# DRV8301_1.net
KiCad netlist of a schematic drawn in Altium Designer
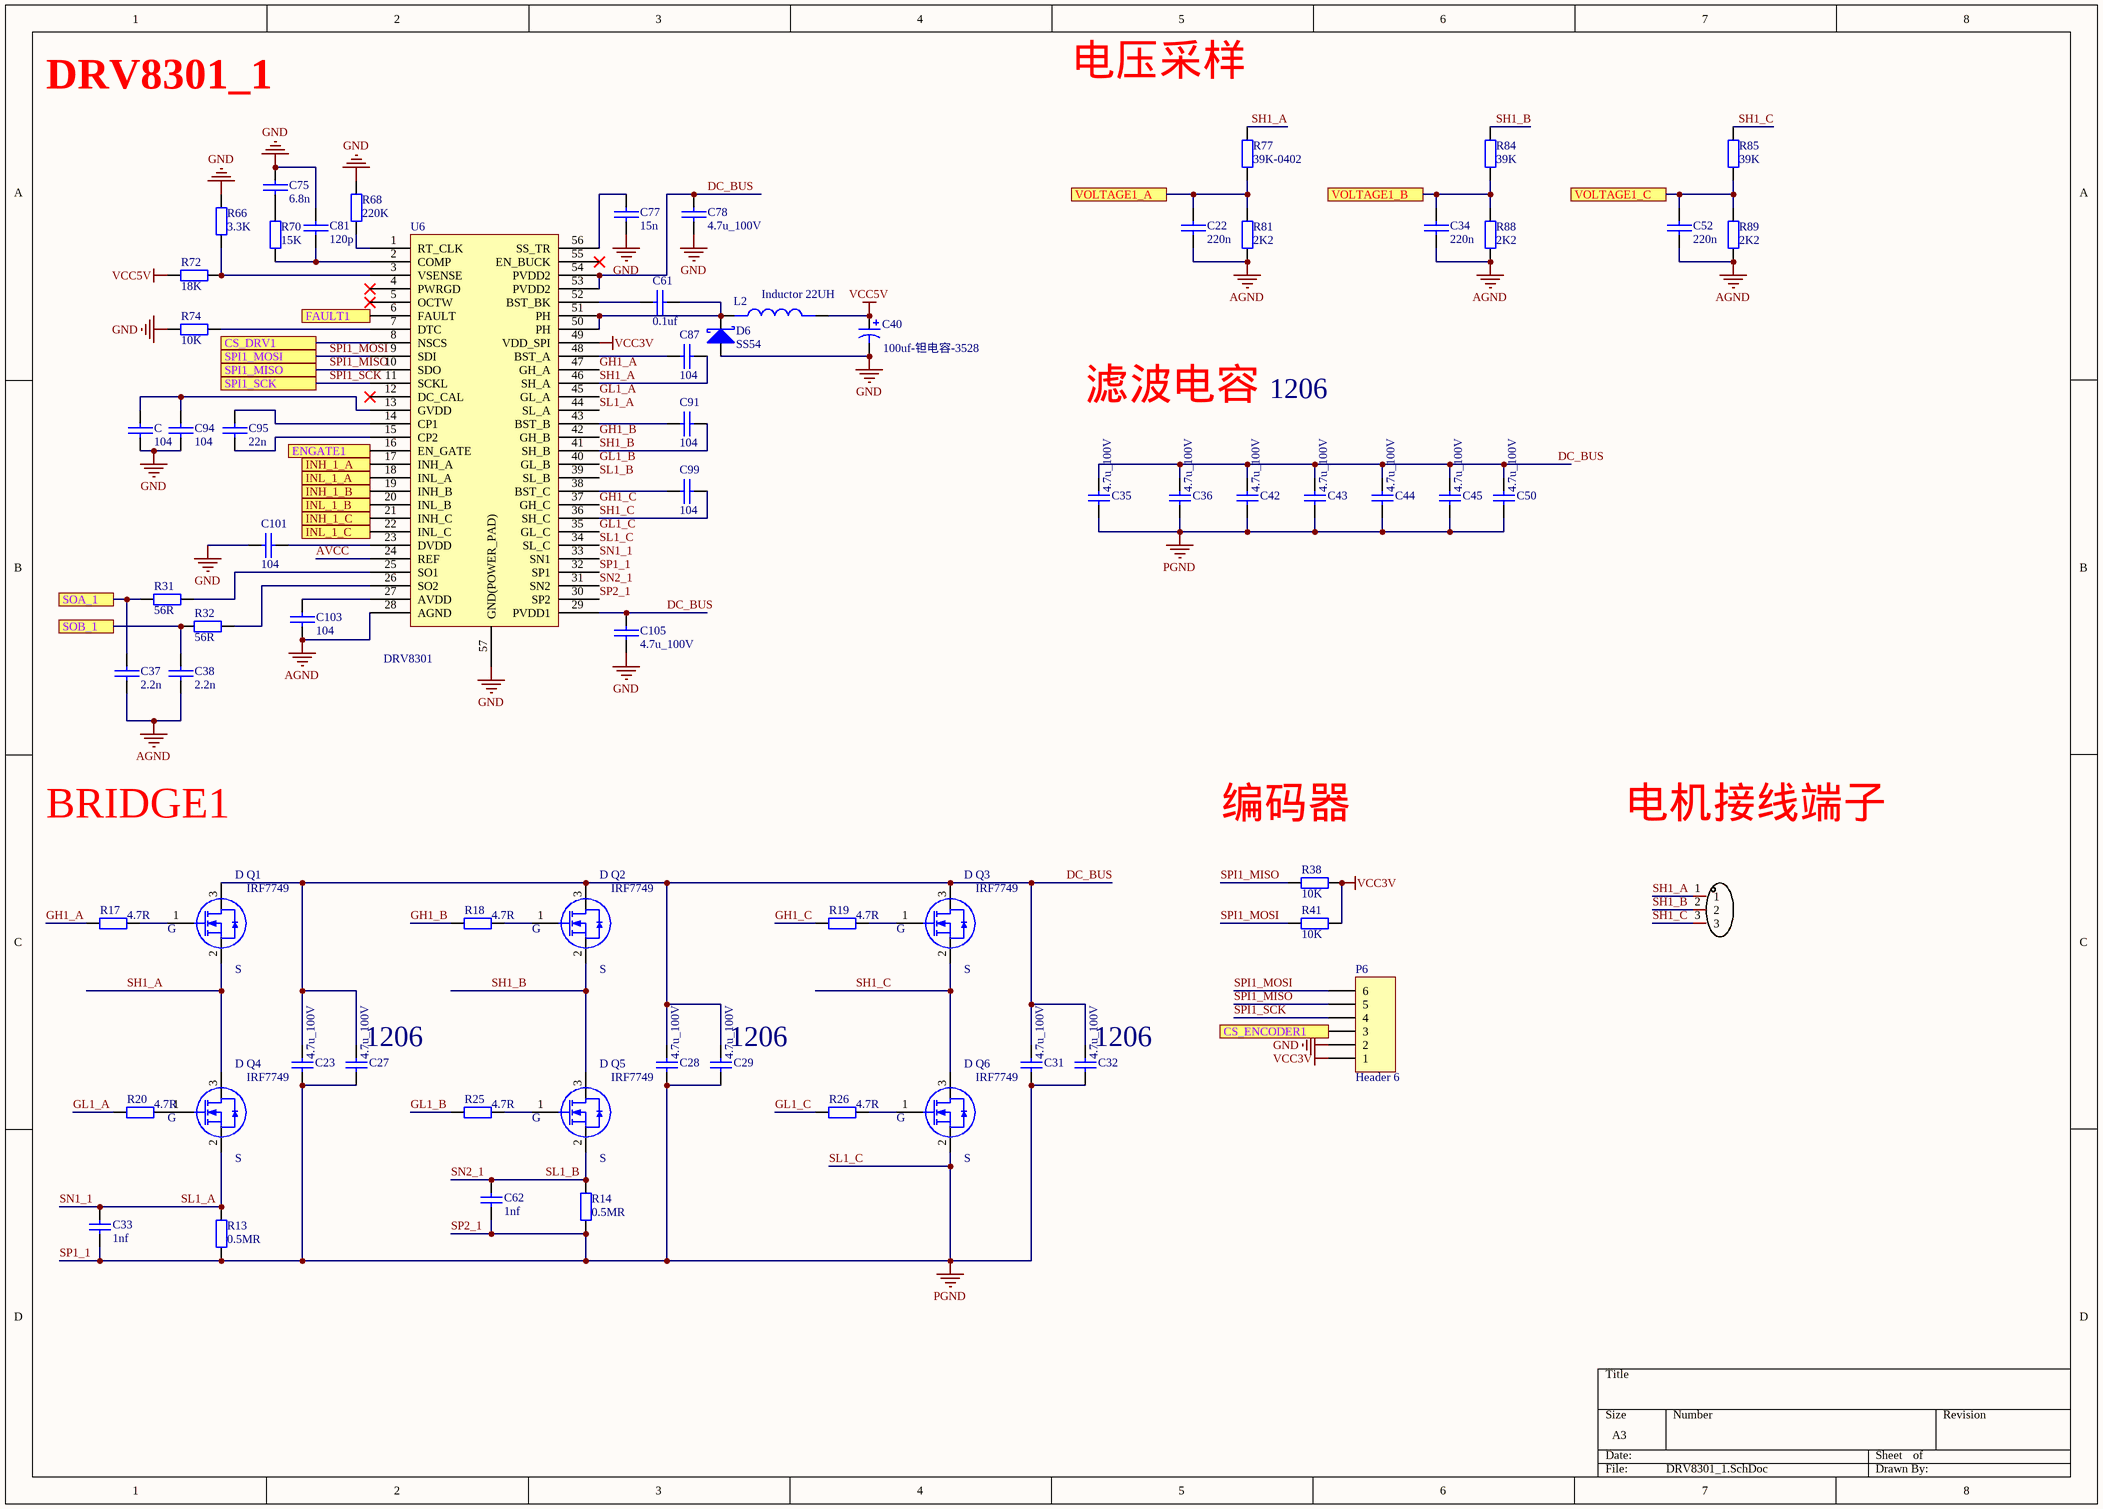
[diagram p0: DRV8301_1.SchDoc]

(export (version "E")
  (design (tool "Eeschema 10.0.6"))
  (components
    (comp (ref "C")
      (value "104")
      (footprint "0402C")
      (fields (field (name "Comment") "CAP"))
      (libsource (lib "MY SCH LIB__JCH") (part "CAP"))
    )
    (comp (ref "C22")
      (value "220n")
      (footprint "0402C")
      (fields (field (name "Comment") "CAP"))
      (libsource (lib "MY SCH LIB__JCH") (part "CAP"))
    )
    (comp (ref "C23")
      (value "4.7u_100V")
      (footprint "1206_C")
      (description "无极性电容")
      (fields (field (name "Comment") "Cap") (field (name "PUBLISHER") "Altium Limited"))
      (libsource (lib "Panel_Point") (part "Cap_6"))
    )
    (comp (ref "C27")
      (value "4.7u_100V")
      (footprint "1206_C")
      (description "无极性电容")
      (fields (field (name "Comment") "Cap") (field (name "PUBLISHER") "Altium Limited"))
      (libsource (lib "Panel_Point") (part "Cap_6"))
    )
    (comp (ref "C28")
      (value "4.7u_100V")
      (footprint "1206_C")
      (description "无极性电容")
      (fields (field (name "Comment") "Cap") (field (name "PUBLISHER") "Altium Limited"))
      (libsource (lib "Panel_Point") (part "Cap_6"))
    )
    (comp (ref "C29")
      (value "4.7u_100V")
      (footprint "1206_C")
      (description "无极性电容")
      (fields (field (name "Comment") "Cap") (field (name "PUBLISHER") "Altium Limited"))
      (libsource (lib "Panel_Point") (part "Cap_6"))
    )
    (comp (ref "C31")
      (value "4.7u_100V")
      (footprint "1206_C")
      (description "无极性电容")
      (fields (field (name "Comment") "Cap") (field (name "PUBLISHER") "Altium Limited"))
      (libsource (lib "Panel_Point") (part "Cap_6"))
    )
    (comp (ref "C32")
      (value "4.7u_100V")
      (footprint "1206_C")
      (description "无极性电容")
      (fields (field (name "Comment") "Cap") (field (name "PUBLISHER") "Altium Limited"))
      (libsource (lib "Panel_Point") (part "Cap_6"))
    )
    (comp (ref "C33")
      (value "1nf")
      (footprint "0402C")
      (description "无极性电容")
      (fields (field (name "Comment") "Cap") (field (name "PUBLISHER") "Altium Limited"))
      (libsource (lib "Panel_Point") (part "Cap_6"))
    )
    (comp (ref "C34")
      (value "220n")
      (footprint "0402C")
      (fields (field (name "Comment") "CAP"))
      (libsource (lib "MY SCH LIB__JCH") (part "CAP"))
    )
    (comp (ref "C35")
      (value "4.7u_100V")
      (footprint "1206_C")
      (description "无极性电容")
      (fields (field (name "Comment") "Cap") (field (name "PUBLISHER") "Altium Limited"))
      (libsource (lib "Panel_Point") (part "Cap_6"))
    )
    (comp (ref "C36")
      (value "4.7u_100V")
      (footprint "1206_C")
      (description "无极性电容")
      (fields (field (name "Comment") "Cap") (field (name "PUBLISHER") "Altium Limited"))
      (libsource (lib "Panel_Point") (part "Cap_6"))
    )
    (comp (ref "C37")
      (value "2.2n")
      (footprint "0402C")
      (fields (field (name "Comment") "CAP"))
      (libsource (lib "MY SCH LIB__JCH") (part "CAP"))
    )
    (comp (ref "C38")
      (value "2.2n")
      (footprint "0402C")
      (fields (field (name "Comment") "CAP"))
      (libsource (lib "MY SCH LIB__JCH") (part "CAP"))
    )
    (comp (ref "C40")
      (value "100uf-钽电容-3528")
      (footprint "CAP-SMD_L3.5-W2.8-R-RD")
      (fields (field (name "Comment") "CAP_HER"))
      (libsource (lib "FOC") (part "CAP_HER"))
    )
    (comp (ref "C42")
      (value "4.7u_100V")
      (footprint "1206_C")
      (description "无极性电容")
      (fields (field (name "Comment") "Cap") (field (name "PUBLISHER") "Altium Limited"))
      (libsource (lib "Panel_Point") (part "Cap_6"))
    )
    (comp (ref "C43")
      (value "4.7u_100V")
      (footprint "1206_C")
      (description "无极性电容")
      (fields (field (name "Comment") "Cap") (field (name "PUBLISHER") "Altium Limited"))
      (libsource (lib "Panel_Point") (part "Cap_6"))
    )
    (comp (ref "C44")
      (value "4.7u_100V")
      (footprint "1206_C")
      (description "无极性电容")
      (fields (field (name "Comment") "Cap") (field (name "PUBLISHER") "Altium Limited"))
      (libsource (lib "Panel_Point") (part "Cap_6"))
    )
    (comp (ref "C45")
      (value "4.7u_100V")
      (footprint "1206_C")
      (description "无极性电容")
      (fields (field (name "Comment") "Cap") (field (name "PUBLISHER") "Altium Limited"))
      (libsource (lib "Panel_Point") (part "Cap_6"))
    )
    (comp (ref "C50")
      (value "4.7u_100V")
      (footprint "1206_C")
      (description "无极性电容")
      (fields (field (name "Comment") "Cap") (field (name "PUBLISHER") "Altium Limited"))
      (libsource (lib "Panel_Point") (part "Cap_6"))
    )
    (comp (ref "C52")
      (value "220n")
      (footprint "0402C")
      (fields (field (name "Comment") "CAP"))
      (libsource (lib "MY SCH LIB__JCH") (part "CAP"))
    )
    (comp (ref "C61")
      (value "0.1uf")
      (footprint "0402C")
      (fields (field (name "Comment") "CAP"))
      (libsource (lib "MY SCH LIB__JCH") (part "CAP"))
    )
    (comp (ref "C62")
      (value "1nf")
      (footprint "0402C")
      (description "无极性电容")
      (fields (field (name "Comment") "Cap") (field (name "PUBLISHER") "Altium Limited"))
      (libsource (lib "Panel_Point") (part "Cap_6"))
    )
    (comp (ref "C75")
      (value "6.8n")
      (footprint "0402C")
      (fields (field (name "Comment") "CAP"))
      (libsource (lib "MY SCH LIB__JCH") (part "CAP"))
    )
    (comp (ref "C77")
      (value "15n")
      (footprint "0402C")
      (fields (field (name "Comment") "CAP"))
      (libsource (lib "MY SCH LIB__JCH") (part "CAP"))
    )
    (comp (ref "C78")
      (value "4.7u_100V")
      (footprint "0603_C")
      (fields (field (name "Comment") "CAP"))
      (libsource (lib "MY SCH LIB__JCH") (part "CAP"))
    )
    (comp (ref "C81")
      (value "120p")
      (footprint "0402C")
      (fields (field (name "Comment") "CAP"))
      (libsource (lib "MY SCH LIB__JCH") (part "CAP"))
    )
    (comp (ref "C87")
      (value "104")
      (footprint "0402C")
      (fields (field (name "Comment") "CAP"))
      (libsource (lib "MY SCH LIB__JCH") (part "CAP"))
    )
    (comp (ref "C91")
      (value "104")
      (footprint "0402C")
      (fields (field (name "Comment") "CAP"))
      (libsource (lib "MY SCH LIB__JCH") (part "CAP"))
    )
    (comp (ref "C94")
      (value "104")
      (footprint "0402C")
      (fields (field (name "Comment") "CAP"))
      (libsource (lib "MY SCH LIB__JCH") (part "CAP"))
    )
    (comp (ref "C95")
      (value "22n")
      (footprint "0402C")
      (fields (field (name "Comment") "CAP"))
      (libsource (lib "MY SCH LIB__JCH") (part "CAP"))
    )
    (comp (ref "C99")
      (value "104")
      (footprint "0402C")
      (fields (field (name "Comment") "CAP"))
      (libsource (lib "MY SCH LIB__JCH") (part "CAP"))
    )
    (comp (ref "C101")
      (value "104")
      (footprint "0402C")
      (fields (field (name "Comment") "CAP"))
      (libsource (lib "MY SCH LIB__JCH") (part "CAP"))
    )
    (comp (ref "C103")
      (value "104")
      (footprint "0402C")
      (fields (field (name "Comment") "CAP"))
      (libsource (lib "MY SCH LIB__JCH") (part "CAP"))
    )
    (comp (ref "C105")
      (value "4.7u_100V")
      (footprint "0603_C")
      (fields (field (name "Comment") "CAP"))
      (libsource (lib "MY SCH LIB__JCH") (part "CAP"))
    )
    (comp (ref "D6")
      (value "SS54")
      (footprint "DIODE_3*5.3")
      (description "Schottky Diode")
      (fields (field (name "PUBLISHER") "Altium Limited"))
      (libsource (lib "FOC") (part "D Schottky"))
    )
    (comp (ref "L2")
      (value "Inductor 22UH")
      (footprint "IND-SMD_L5.0-W5.0")
      (libsource (lib "Panel_Point") (part "IND"))
    )
    (comp (ref "P6")
      (value "Header 6")
      (footprint "A1002WR-S-6P")
      (description "Header, 6-Pin")
      (fields (field (name "PUBLISHER") "Altium Limited"))
      (libsource (lib "FOC") (part "Header 6"))
    )
    (comp (ref "Q1")
      (value "IRF7749")
      (footprint "IRF7480")
      (description "MOS(场效应管)")
      (libsource (lib "FOC") (part "IRF7749"))
    )
    (comp (ref "Q2")
      (value "IRF7749")
      (footprint "IRF7480")
      (description "MOS(场效应管)")
      (libsource (lib "FOC") (part "IRF7749"))
    )
    (comp (ref "Q3")
      (value "IRF7749")
      (footprint "IRF7480")
      (description "MOS(场效应管)")
      (libsource (lib "FOC") (part "IRF7749"))
    )
    (comp (ref "Q4")
      (value "IRF7749")
      (footprint "IRF7480")
      (description "MOS(场效应管)")
      (libsource (lib "FOC") (part "IRF7749"))
    )
    (comp (ref "Q5")
      (value "IRF7749")
      (footprint "IRF7480")
      (description "MOS(场效应管)")
      (libsource (lib "FOC") (part "IRF7749"))
    )
    (comp (ref "Q6")
      (value "IRF7749")
      (footprint "IRF7480")
      (description "MOS(场效应管)")
      (libsource (lib "FOC") (part "IRF7749"))
    )
    (comp (ref "R13")
      (value "0.5MR")
      (footprint "0.5mr_6W")
      (description "贴片电阻")
      (fields (field (name "Comment") "Res1") (field (name "PUBLISHER") "Altium Limited"))
      (libsource (lib "SMC_Devices") (part "Res1"))
    )
    (comp (ref "R14")
      (value "0.5MR")
      (footprint "0.5mr_6W")
      (description "贴片电阻")
      (fields (field (name "Comment") "Res1") (field (name "PUBLISHER") "Altium Limited"))
      (libsource (lib "SMC_Devices") (part "Res1"))
    )
    (comp (ref "R17")
      (value "4.7R")
      (footprint "0402R")
      (description "贴片电阻")
      (fields (field (name "Comment") "Res1") (field (name "PUBLISHER") "Altium Limited"))
      (libsource (lib "") (part "Res1_1"))
    )
    (comp (ref "R18")
      (value "4.7R")
      (footprint "0402R")
      (description "贴片电阻")
      (fields (field (name "Comment") "Res1") (field (name "PUBLISHER") "Altium Limited"))
      (libsource (lib "") (part "Res1_1"))
    )
    (comp (ref "R19")
      (value "4.7R")
      (footprint "0402R")
      (description "贴片电阻")
      (fields (field (name "Comment") "Res1") (field (name "PUBLISHER") "Altium Limited"))
      (libsource (lib "") (part "Res1_1"))
    )
    (comp (ref "R20")
      (value "4.7R")
      (footprint "0402R")
      (description "贴片电阻")
      (fields (field (name "Comment") "Res1") (field (name "PUBLISHER") "Altium Limited"))
      (libsource (lib "") (part "Res1_1"))
    )
    (comp (ref "R25")
      (value "4.7R")
      (footprint "0402R")
      (description "贴片电阻")
      (fields (field (name "Comment") "Res1") (field (name "PUBLISHER") "Altium Limited"))
      (libsource (lib "") (part "Res1_1"))
    )
    (comp (ref "R26")
      (value "4.7R")
      (footprint "0402R")
      (description "贴片电阻")
      (fields (field (name "Comment") "Res1") (field (name "PUBLISHER") "Altium Limited"))
      (libsource (lib "") (part "Res1_1"))
    )
    (comp (ref "R31")
      (value "56R")
      (footprint "0402R")
      (description "Resistor")
      (fields (field (name "PUBLISHER") "Altium Limited"))
      (libsource (lib "") (part "Res2_2"))
    )
    (comp (ref "R32")
      (value "56R")
      (footprint "0402R")
      (description "Resistor")
      (fields (field (name "PUBLISHER") "Altium Limited"))
      (libsource (lib "") (part "Res2_2"))
    )
    (comp (ref "R38")
      (value "10K")
      (footprint "0402R")
      (description "Resistor")
      (fields (field (name "PUBLISHER") "Altium Limited"))
      (libsource (lib "") (part "Res2_2"))
    )
    (comp (ref "R41")
      (value "10K")
      (footprint "0402R")
      (description "Resistor")
      (fields (field (name "PUBLISHER") "Altium Limited"))
      (libsource (lib "") (part "Res2_2"))
    )
    (comp (ref "R66")
      (value "3.3K")
      (footprint "0402R")
      (description "Resistor")
      (fields (field (name "PUBLISHER") "Altium Limited"))
      (libsource (lib "") (part "Res2_1"))
    )
    (comp (ref "R68")
      (value "220K")
      (footprint "0402R")
      (description "Resistor")
      (fields (field (name "PUBLISHER") "Altium Limited"))
      (libsource (lib "") (part "Res2_1"))
    )
    (comp (ref "R70")
      (value "15K")
      (footprint "0402R")
      (description "Resistor")
      (fields (field (name "PUBLISHER") "Altium Limited"))
      (libsource (lib "") (part "Res2_1"))
    )
    (comp (ref "R72")
      (value "18K")
      (footprint "0402R")
      (description "Resistor")
      (fields (field (name "PUBLISHER") "Altium Limited"))
      (libsource (lib "") (part "Res2_2"))
    )
    (comp (ref "R74")
      (value "10K")
      (footprint "0402R")
      (description "Resistor")
      (fields (field (name "PUBLISHER") "Altium Limited"))
      (libsource (lib "") (part "Res2_2"))
    )
    (comp (ref "R77")
      (value "39K-0402")
      (footprint "0402R")
      (description "Resistor")
      (fields (field (name "PUBLISHER") "Altium Limited"))
      (libsource (lib "") (part "Res2_1"))
    )
    (comp (ref "R81")
      (value "2K2")
      (footprint "0402R")
      (description "Resistor")
      (fields (field (name "PUBLISHER") "Altium Limited"))
      (libsource (lib "Miscellaneous Devices") (part "Res2"))
    )
    (comp (ref "R84")
      (value "39K")
      (footprint "0402R")
      (description "Resistor")
      (fields (field (name "PUBLISHER") "Altium Limited"))
      (libsource (lib "") (part "Res2_1"))
    )
    (comp (ref "R85")
      (value "39K")
      (footprint "0402R")
      (description "Resistor")
      (fields (field (name "PUBLISHER") "Altium Limited"))
      (libsource (lib "") (part "Res2_1"))
    )
    (comp (ref "R88")
      (value "2K2")
      (footprint "0402R")
      (description "Resistor")
      (fields (field (name "PUBLISHER") "Altium Limited"))
      (libsource (lib "Miscellaneous Devices") (part "Res2"))
    )
    (comp (ref "R89")
      (value "2K2")
      (footprint "0402R")
      (description "Resistor")
      (fields (field (name "PUBLISHER") "Altium Limited"))
      (libsource (lib "Miscellaneous Devices") (part "Res2"))
    )
    (comp (ref "U6")
      (value "DRV8301")
      (footprint "HTSSOP-56_L14.0-W6.0-P0.50-LS8.0-BL")
      (description "三相整流桥芯片")
      (libsource (lib "FOC") (part "DRV8301"))
    )
    (comp (ref "U7")
      (value "MR30-M")
      (footprint "MR30-M-SMD")
      (fields (field (name "MANUFACTURER") "AMASS(艾迈斯)"))
      (libsource (lib "FOC") (part "MR30-M"))
    )
  )
  (nets
    (net (code "1") (name "/AVCC") (class "Default")
      (node (ref "U6") (pin "24") (pinfunction "REF_24") (pintype "passive"))
    )
    (net (code "2") (name "/CS_DRV1") (class "Default")
      (node (ref "U6") (pin "8") (pinfunction "NSCS_8") (pintype "passive"))
    )
    (net (code "3") (name "/CS_ENCODER1") (class "Default")
      (node (ref "P6") (pin "3") (pinfunction "3_3") (pintype "passive"))
    )
    (net (code "4") (name "/DC_BUS") (class "Default")
      (node (ref "C105") (pin "2") (pinfunction "2_2") (pintype "passive"))
      (node (ref "C23") (pin "2") (pinfunction "2_2") (pintype "passive"))
      (node (ref "C27") (pin "2") (pinfunction "2_2") (pintype "passive"))
      (node (ref "C28") (pin "2") (pinfunction "2_2") (pintype "passive"))
      (node (ref "C29") (pin "2") (pinfunction "2_2") (pintype "passive"))
      (node (ref "C31") (pin "2") (pinfunction "2_2") (pintype "passive"))
      (node (ref "C32") (pin "2") (pinfunction "2_2") (pintype "passive"))
      (node (ref "C35") (pin "2") (pinfunction "2_2") (pintype "passive"))
      (node (ref "C36") (pin "2") (pinfunction "2_2") (pintype "passive"))
      (node (ref "C42") (pin "2") (pinfunction "2_2") (pintype "passive"))
      (node (ref "C43") (pin "2") (pinfunction "2_2") (pintype "passive"))
      (node (ref "C44") (pin "2") (pinfunction "2_2") (pintype "passive"))
      (node (ref "C45") (pin "2") (pinfunction "2_2") (pintype "passive"))
      (node (ref "C50") (pin "2") (pinfunction "2_2") (pintype "passive"))
      (node (ref "C78") (pin "2") (pinfunction "2_2") (pintype "passive"))
      (node (ref "Q1") (pin "3") (pinfunction "D_3") (pintype "passive"))
      (node (ref "Q2") (pin "3") (pinfunction "D_3") (pintype "passive"))
      (node (ref "Q3") (pin "3") (pinfunction "D_3") (pintype "passive"))
      (node (ref "U6") (pin "29") (pinfunction "PVDD1_29") (pintype "passive"))
      (node (ref "U6") (pin "53") (pinfunction "PVDD2_53") (pintype "passive"))
      (node (ref "U6") (pin "54") (pinfunction "PVDD2_54") (pintype "passive"))
    )
    (net (code "5") (name "/ENGATE1") (class "Default")
      (node (ref "U6") (pin "16") (pinfunction "EN_GATE_16") (pintype "passive"))
    )
    (net (code "6") (name "/FAULT1") (class "Default")
      (node (ref "U6") (pin "6") (pinfunction "FAULT_6") (pintype "passive"))
    )
    (net (code "7") (name "/GH1_A") (class "Default")
      (node (ref "R17") (pin "1") (pinfunction "1_1") (pintype "passive"))
      (node (ref "U6") (pin "47") (pinfunction "GH_A_47") (pintype "passive"))
    )
    (net (code "8") (name "/GH1_B") (class "Default")
      (node (ref "R18") (pin "1") (pinfunction "1_1") (pintype "passive"))
      (node (ref "U6") (pin "42") (pinfunction "GH_B_42") (pintype "passive"))
    )
    (net (code "9") (name "/GH1_C") (class "Default")
      (node (ref "R19") (pin "1") (pinfunction "1_1") (pintype "passive"))
      (node (ref "U6") (pin "37") (pinfunction "GH_C_37") (pintype "passive"))
    )
    (net (code "10") (name "/GL1_A") (class "Default")
      (node (ref "R20") (pin "1") (pinfunction "1_1") (pintype "passive"))
      (node (ref "U6") (pin "45") (pinfunction "GL_A_45") (pintype "passive"))
    )
    (net (code "11") (name "/GL1_B") (class "Default")
      (node (ref "R25") (pin "1") (pinfunction "1_1") (pintype "passive"))
      (node (ref "U6") (pin "40") (pinfunction "GL_B_40") (pintype "passive"))
    )
    (net (code "12") (name "/GL1_C") (class "Default")
      (node (ref "R26") (pin "1") (pinfunction "1_1") (pintype "passive"))
      (node (ref "U6") (pin "35") (pinfunction "GL_C_35") (pintype "passive"))
    )
    (net (code "13") (name "/INH_1_A") (class "Default")
      (node (ref "U6") (pin "17") (pinfunction "INH_A_17") (pintype "passive"))
    )
    (net (code "14") (name "/INH_1_B") (class "Default")
      (node (ref "U6") (pin "19") (pinfunction "INH_B_19") (pintype "passive"))
    )
    (net (code "15") (name "/INH_1_C") (class "Default")
      (node (ref "U6") (pin "21") (pinfunction "INH_C_21") (pintype "passive"))
    )
    (net (code "16") (name "/INL_1_A") (class "Default")
      (node (ref "U6") (pin "18") (pinfunction "INL_A_18") (pintype "passive"))
    )
    (net (code "17") (name "/INL_1_B") (class "Default")
      (node (ref "U6") (pin "20") (pinfunction "INL_B_20") (pintype "passive"))
    )
    (net (code "18") (name "/INL_1_C") (class "Default")
      (node (ref "U6") (pin "22") (pinfunction "INL_C_22") (pintype "passive"))
    )
    (net (code "19") (name "/SH1_A") (class "Default")
      (node (ref "C87") (pin "1") (pinfunction "1_1") (pintype "passive"))
      (node (ref "Q1") (pin "2") (pinfunction "S_2") (pintype "passive"))
      (node (ref "Q4") (pin "3") (pinfunction "D_3") (pintype "passive"))
      (node (ref "R77") (pin "2") (pinfunction "2_2") (pintype "passive"))
      (node (ref "U6") (pin "46") (pinfunction "SH_A_46") (pintype "passive"))
      (node (ref "U7") (pin "1") (pinfunction "1_1") (pintype "passive"))
    )
    (net (code "20") (name "/SH1_B") (class "Default")
      (node (ref "C91") (pin "1") (pinfunction "1_1") (pintype "passive"))
      (node (ref "Q2") (pin "2") (pinfunction "S_2") (pintype "passive"))
      (node (ref "Q5") (pin "3") (pinfunction "D_3") (pintype "passive"))
      (node (ref "R84") (pin "2") (pinfunction "2_2") (pintype "passive"))
      (node (ref "U6") (pin "41") (pinfunction "SH_B_41") (pintype "passive"))
      (node (ref "U7") (pin "2") (pinfunction "2_2") (pintype "passive"))
    )
    (net (code "21") (name "/SH1_C") (class "Default")
      (node (ref "C99") (pin "1") (pinfunction "1_1") (pintype "passive"))
      (node (ref "Q3") (pin "2") (pinfunction "S_2") (pintype "passive"))
      (node (ref "Q6") (pin "3") (pinfunction "D_3") (pintype "passive"))
      (node (ref "R85") (pin "2") (pinfunction "2_2") (pintype "passive"))
      (node (ref "U6") (pin "36") (pinfunction "SH_C_36") (pintype "passive"))
      (node (ref "U7") (pin "3") (pinfunction "3_3") (pintype "passive"))
    )
    (net (code "22") (name "/SL1_A") (class "Default")
      (node (ref "C33") (pin "2") (pinfunction "2_2") (pintype "passive"))
      (node (ref "Q4") (pin "2") (pinfunction "S_2") (pintype "passive"))
      (node (ref "R13") (pin "2") (pinfunction "2_2") (pintype "passive"))
      (node (ref "U6") (pin "33") (pinfunction "SN1_33") (pintype "passive"))
      (node (ref "U6") (pin "44") (pinfunction "SL_A_44") (pintype "passive"))
    )
    (net (code "23") (name "/SL1_B") (class "Default")
      (node (ref "C62") (pin "2") (pinfunction "2_2") (pintype "passive"))
      (node (ref "Q5") (pin "2") (pinfunction "S_2") (pintype "passive"))
      (node (ref "R14") (pin "2") (pinfunction "2_2") (pintype "passive"))
      (node (ref "U6") (pin "31") (pinfunction "SN2_31") (pintype "passive"))
      (node (ref "U6") (pin "39") (pinfunction "SL_B_39") (pintype "passive"))
    )
    (net (code "24") (name "/SOA_1") (class "Default")
      (node (ref "C37") (pin "2") (pinfunction "2_2") (pintype "passive"))
      (node (ref "R31") (pin "1") (pinfunction "1_1") (pintype "passive"))
    )
    (net (code "25") (name "/SOB_1") (class "Default")
      (node (ref "C38") (pin "2") (pinfunction "2_2") (pintype "passive"))
      (node (ref "R32") (pin "1") (pinfunction "1_1") (pintype "passive"))
    )
    (net (code "26") (name "/SPI1_MISO") (class "Default")
      (node (ref "P6") (pin "5") (pinfunction "5_5") (pintype "passive"))
      (node (ref "R38") (pin "1") (pinfunction "1_1") (pintype "passive"))
      (node (ref "U6") (pin "10") (pinfunction "SDO_10") (pintype "passive"))
    )
    (net (code "27") (name "/SPI1_MOSI") (class "Default")
      (node (ref "P6") (pin "6") (pinfunction "6_6") (pintype "passive"))
      (node (ref "R41") (pin "1") (pinfunction "1_1") (pintype "passive"))
      (node (ref "U6") (pin "9") (pinfunction "SDI_9") (pintype "passive"))
    )
    (net (code "28") (name "/SPI1_SCK") (class "Default")
      (node (ref "P6") (pin "4") (pinfunction "4_4") (pintype "passive"))
      (node (ref "U6") (pin "11") (pinfunction "SCKL_11") (pintype "passive"))
    )
    (net (code "29") (name "/VOLTAGE1_A") (class "Default")
      (node (ref "C22") (pin "1") (pinfunction "1_1") (pintype "passive"))
      (node (ref "R77") (pin "1") (pinfunction "1_1") (pintype "passive"))
      (node (ref "R81") (pin "1") (pinfunction "1_1") (pintype "passive"))
    )
    (net (code "30") (name "/VOLTAGE1_B") (class "Default")
      (node (ref "C34") (pin "1") (pinfunction "1_1") (pintype "passive"))
      (node (ref "R84") (pin "1") (pinfunction "1_1") (pintype "passive"))
      (node (ref "R88") (pin "1") (pinfunction "1_1") (pintype "passive"))
    )
    (net (code "31") (name "/VOLTAGE1_C") (class "Default")
      (node (ref "C52") (pin "1") (pinfunction "1_1") (pintype "passive"))
      (node (ref "R85") (pin "1") (pinfunction "1_1") (pintype "passive"))
      (node (ref "R89") (pin "1") (pinfunction "1_1") (pintype "passive"))
    )
    (net (code "32") (name "AGND") (class "Default")
      (node (ref "C103") (pin "1") (pinfunction "1_1") (pintype "passive"))
      (node (ref "C22") (pin "2") (pinfunction "2_2") (pintype "passive"))
      (node (ref "C34") (pin "2") (pinfunction "2_2") (pintype "passive"))
      (node (ref "C37") (pin "1") (pinfunction "1_1") (pintype "passive"))
      (node (ref "C38") (pin "1") (pinfunction "1_1") (pintype "passive"))
      (node (ref "C52") (pin "2") (pinfunction "2_2") (pintype "passive"))
      (node (ref "R81") (pin "2") (pinfunction "2_2") (pintype "passive"))
      (node (ref "R88") (pin "2") (pinfunction "2_2") (pintype "passive"))
      (node (ref "R89") (pin "2") (pinfunction "2_2") (pintype "passive"))
      (node (ref "U6") (pin "28") (pinfunction "AGND_28") (pintype "passive"))
    )
    (net (code "33") (name "GND") (class "Default")
      (node (ref "C") (pin "1") (pinfunction "1_1") (pintype "passive"))
      (node (ref "C101") (pin "1") (pinfunction "1_1") (pintype "passive"))
      (node (ref "C105") (pin "1") (pinfunction "1_1") (pintype "passive"))
      (node (ref "C40") (pin "2") (pinfunction "2_2") (pintype "passive"))
      (node (ref "C75") (pin "2") (pinfunction "2_2") (pintype "passive"))
      (node (ref "C77") (pin "1") (pinfunction "1_1") (pintype "passive"))
      (node (ref "C78") (pin "1") (pinfunction "1_1") (pintype "passive"))
      (node (ref "C81") (pin "2") (pinfunction "2_2") (pintype "passive"))
      (node (ref "C94") (pin "1") (pinfunction "1_1") (pintype "passive"))
      (node (ref "D6") (pin "1") (pinfunction "A_1") (pintype "passive"))
      (node (ref "P6") (pin "2") (pinfunction "2_2") (pintype "passive"))
      (node (ref "R66") (pin "2") (pinfunction "2_2") (pintype "passive"))
      (node (ref "R68") (pin "2") (pinfunction "2_2") (pintype "passive"))
      (node (ref "R74") (pin "1") (pinfunction "1_1") (pintype "passive"))
      (node (ref "U6") (pin "57") (pinfunction "GND(POWER_PAD)_57") (pintype "passive"))
    )
    (net (code "34") (name "Net-(C75-Pad1)") (class "Default")
      (node (ref "C75") (pin "1") (pinfunction "1_1") (pintype "passive"))
      (node (ref "R70") (pin "2") (pinfunction "2_2") (pintype "passive"))
    )
    (net (code "35") (name "Net-(D6-K)") (class "Default")
      (node (ref "C61") (pin "1") (pinfunction "1_1") (pintype "passive"))
      (node (ref "D6") (pin "2") (pinfunction "K_2") (pintype "passive"))
      (node (ref "L2") (pin "1") (pinfunction "Pri-_1") (pintype "passive"))
      (node (ref "U6") (pin "50") (pinfunction "PH_50") (pintype "passive"))
      (node (ref "U6") (pin "51") (pinfunction "PH_51") (pintype "passive"))
    )
    (net (code "36") (name "Net-(Q1-G)") (class "Default")
      (node (ref "Q1") (pin "1") (pinfunction "G_1") (pintype "passive"))
      (node (ref "R17") (pin "2") (pinfunction "2_2") (pintype "passive"))
    )
    (net (code "37") (name "Net-(Q2-G)") (class "Default")
      (node (ref "Q2") (pin "1") (pinfunction "G_1") (pintype "passive"))
      (node (ref "R18") (pin "2") (pinfunction "2_2") (pintype "passive"))
    )
    (net (code "38") (name "Net-(Q3-G)") (class "Default")
      (node (ref "Q3") (pin "1") (pinfunction "G_1") (pintype "passive"))
      (node (ref "R19") (pin "2") (pinfunction "2_2") (pintype "passive"))
    )
    (net (code "39") (name "Net-(Q4-G)") (class "Default")
      (node (ref "Q4") (pin "1") (pinfunction "G_1") (pintype "passive"))
      (node (ref "R20") (pin "2") (pinfunction "2_2") (pintype "passive"))
    )
    (net (code "40") (name "Net-(Q5-G)") (class "Default")
      (node (ref "Q5") (pin "1") (pinfunction "G_1") (pintype "passive"))
      (node (ref "R25") (pin "2") (pinfunction "2_2") (pintype "passive"))
    )
    (net (code "41") (name "Net-(Q6-G)") (class "Default")
      (node (ref "Q6") (pin "1") (pinfunction "G_1") (pintype "passive"))
      (node (ref "R26") (pin "2") (pinfunction "2_2") (pintype "passive"))
    )
    (net (code "42") (name "Net-(U6-AVDD)") (class "Default")
      (node (ref "C103") (pin "2") (pinfunction "2_2") (pintype "passive"))
      (node (ref "U6") (pin "27") (pinfunction "AVDD_27") (pintype "passive"))
    )
    (net (code "43") (name "Net-(U6-BST_A)") (class "Default")
      (node (ref "C87") (pin "2") (pinfunction "2_2") (pintype "passive"))
      (node (ref "U6") (pin "48") (pinfunction "BST_A_48") (pintype "passive"))
    )
    (net (code "44") (name "Net-(U6-BST_B)") (class "Default")
      (node (ref "C91") (pin "2") (pinfunction "2_2") (pintype "passive"))
      (node (ref "U6") (pin "43") (pinfunction "BST_B_43") (pintype "passive"))
    )
    (net (code "45") (name "Net-(U6-BST_BK)") (class "Default")
      (node (ref "C61") (pin "2") (pinfunction "2_2") (pintype "passive"))
      (node (ref "U6") (pin "52") (pinfunction "BST_BK_52") (pintype "passive"))
    )
    (net (code "46") (name "Net-(U6-BST_C)") (class "Default")
      (node (ref "C99") (pin "2") (pinfunction "2_2") (pintype "passive"))
      (node (ref "U6") (pin "38") (pinfunction "BST_C_38") (pintype "passive"))
    )
    (net (code "47") (name "Net-(U6-COMP)") (class "Default")
      (node (ref "C81") (pin "1") (pinfunction "1_1") (pintype "passive"))
      (node (ref "R70") (pin "1") (pinfunction "1_1") (pintype "passive"))
      (node (ref "U6") (pin "2") (pinfunction "COMP_2") (pintype "passive"))
    )
    (net (code "48") (name "Net-(U6-CP1)") (class "Default")
      (node (ref "C95") (pin "1") (pinfunction "1_1") (pintype "passive"))
      (node (ref "U6") (pin "14") (pinfunction "CP1_14") (pintype "passive"))
    )
    (net (code "49") (name "Net-(U6-CP2)") (class "Default")
      (node (ref "C95") (pin "2") (pinfunction "2_2") (pintype "passive"))
      (node (ref "U6") (pin "15") (pinfunction "CP2_15") (pintype "passive"))
    )
    (net (code "50") (name "Net-(U6-DTC)") (class "Default")
      (node (ref "R74") (pin "2") (pinfunction "2_2") (pintype "passive"))
      (node (ref "U6") (pin "7") (pinfunction "DTC_7") (pintype "passive"))
    )
    (net (code "51") (name "Net-(U6-DVDD)") (class "Default")
      (node (ref "C101") (pin "2") (pinfunction "2_2") (pintype "passive"))
      (node (ref "U6") (pin "23") (pinfunction "DVDD_23") (pintype "passive"))
    )
    (net (code "52") (name "Net-(U6-GVDD)") (class "Default")
      (node (ref "C") (pin "2") (pinfunction "2_2") (pintype "passive"))
      (node (ref "C94") (pin "2") (pinfunction "2_2") (pintype "passive"))
      (node (ref "U6") (pin "13") (pinfunction "GVDD_13") (pintype "passive"))
    )
    (net (code "53") (name "Net-(U6-RT_CLK)") (class "Default")
      (node (ref "R68") (pin "1") (pinfunction "1_1") (pintype "passive"))
      (node (ref "U6") (pin "1") (pinfunction "RT_CLK_1") (pintype "passive"))
    )
    (net (code "54") (name "Net-(U6-SO1)") (class "Default")
      (node (ref "R31") (pin "2") (pinfunction "2_2") (pintype "passive"))
      (node (ref "U6") (pin "25") (pinfunction "SO1_25") (pintype "passive"))
    )
    (net (code "55") (name "Net-(U6-SO2)") (class "Default")
      (node (ref "R32") (pin "2") (pinfunction "2_2") (pintype "passive"))
      (node (ref "U6") (pin "26") (pinfunction "SO2_26") (pintype "passive"))
    )
    (net (code "56") (name "Net-(U6-SS_TR)") (class "Default")
      (node (ref "C77") (pin "2") (pinfunction "2_2") (pintype "passive"))
      (node (ref "U6") (pin "56") (pinfunction "SS_TR_56") (pintype "passive"))
    )
    (net (code "57") (name "Net-(U6-VSENSE)") (class "Default")
      (node (ref "R66") (pin "1") (pinfunction "1_1") (pintype "passive"))
      (node (ref "R72") (pin "2") (pinfunction "2_2") (pintype "passive"))
      (node (ref "U6") (pin "3") (pinfunction "VSENSE_3") (pintype "passive"))
    )
    (net (code "58") (name "PGND") (class "Default")
      (node (ref "C23") (pin "1") (pinfunction "1_1") (pintype "passive"))
      (node (ref "C27") (pin "1") (pinfunction "1_1") (pintype "passive"))
      (node (ref "C28") (pin "1") (pinfunction "1_1") (pintype "passive"))
      (node (ref "C29") (pin "1") (pinfunction "1_1") (pintype "passive"))
      (node (ref "C31") (pin "1") (pinfunction "1_1") (pintype "passive"))
      (node (ref "C32") (pin "1") (pinfunction "1_1") (pintype "passive"))
      (node (ref "C33") (pin "1") (pinfunction "1_1") (pintype "passive"))
      (node (ref "C35") (pin "1") (pinfunction "1_1") (pintype "passive"))
      (node (ref "C36") (pin "1") (pinfunction "1_1") (pintype "passive"))
      (node (ref "C42") (pin "1") (pinfunction "1_1") (pintype "passive"))
      (node (ref "C43") (pin "1") (pinfunction "1_1") (pintype "passive"))
      (node (ref "C44") (pin "1") (pinfunction "1_1") (pintype "passive"))
      (node (ref "C45") (pin "1") (pinfunction "1_1") (pintype "passive"))
      (node (ref "C50") (pin "1") (pinfunction "1_1") (pintype "passive"))
      (node (ref "C62") (pin "1") (pinfunction "1_1") (pintype "passive"))
      (node (ref "Q6") (pin "2") (pinfunction "S_2") (pintype "passive"))
      (node (ref "R13") (pin "1") (pinfunction "1_1") (pintype "passive"))
      (node (ref "R14") (pin "1") (pinfunction "1_1") (pintype "passive"))
      (node (ref "U6") (pin "30") (pinfunction "SP2_30") (pintype "passive"))
      (node (ref "U6") (pin "32") (pinfunction "SP1_32") (pintype "passive"))
      (node (ref "U6") (pin "34") (pinfunction "SL_C_34") (pintype "passive"))
    )
    (net (code "59") (name "VCC3V") (class "Default")
      (node (ref "P6") (pin "1") (pinfunction "1_1") (pintype "passive"))
      (node (ref "R38") (pin "2") (pinfunction "2_2") (pintype "passive"))
      (node (ref "R41") (pin "2") (pinfunction "2_2") (pintype "passive"))
      (node (ref "U6") (pin "49") (pinfunction "VDD_SPI_49") (pintype "passive"))
    )
    (net (code "60") (name "VCC5V") (class "Default")
      (node (ref "C40") (pin "1") (pinfunction "1_1") (pintype "passive"))
      (node (ref "L2") (pin "2") (pinfunction "Pri-_2") (pintype "passive"))
      (node (ref "R72") (pin "1") (pinfunction "1_1") (pintype "passive"))
    )
    (net (code "61") (name "unconnected-(U6-DC_CAL-Pad12)") (class "Default")
      (node (ref "U6") (pin "12") (pinfunction "DC_CAL_12") (pintype "passive+no_connect"))
    )
    (net (code "62") (name "unconnected-(U6-EN_BUCK-Pad55)") (class "Default")
      (node (ref "U6") (pin "55") (pinfunction "EN_BUCK_55") (pintype "passive+no_connect"))
    )
    (net (code "63") (name "unconnected-(U6-OCTW-Pad5)") (class "Default")
      (node (ref "U6") (pin "5") (pinfunction "OCTW_5") (pintype "passive+no_connect"))
    )
    (net (code "64") (name "unconnected-(U6-PWRGD-Pad4)") (class "Default")
      (node (ref "U6") (pin "4") (pinfunction "PWRGD_4") (pintype "passive+no_connect"))
    )
  )
)
